# bmscableL431.net
KiCad netlist of a schematic drawn in EAGLE
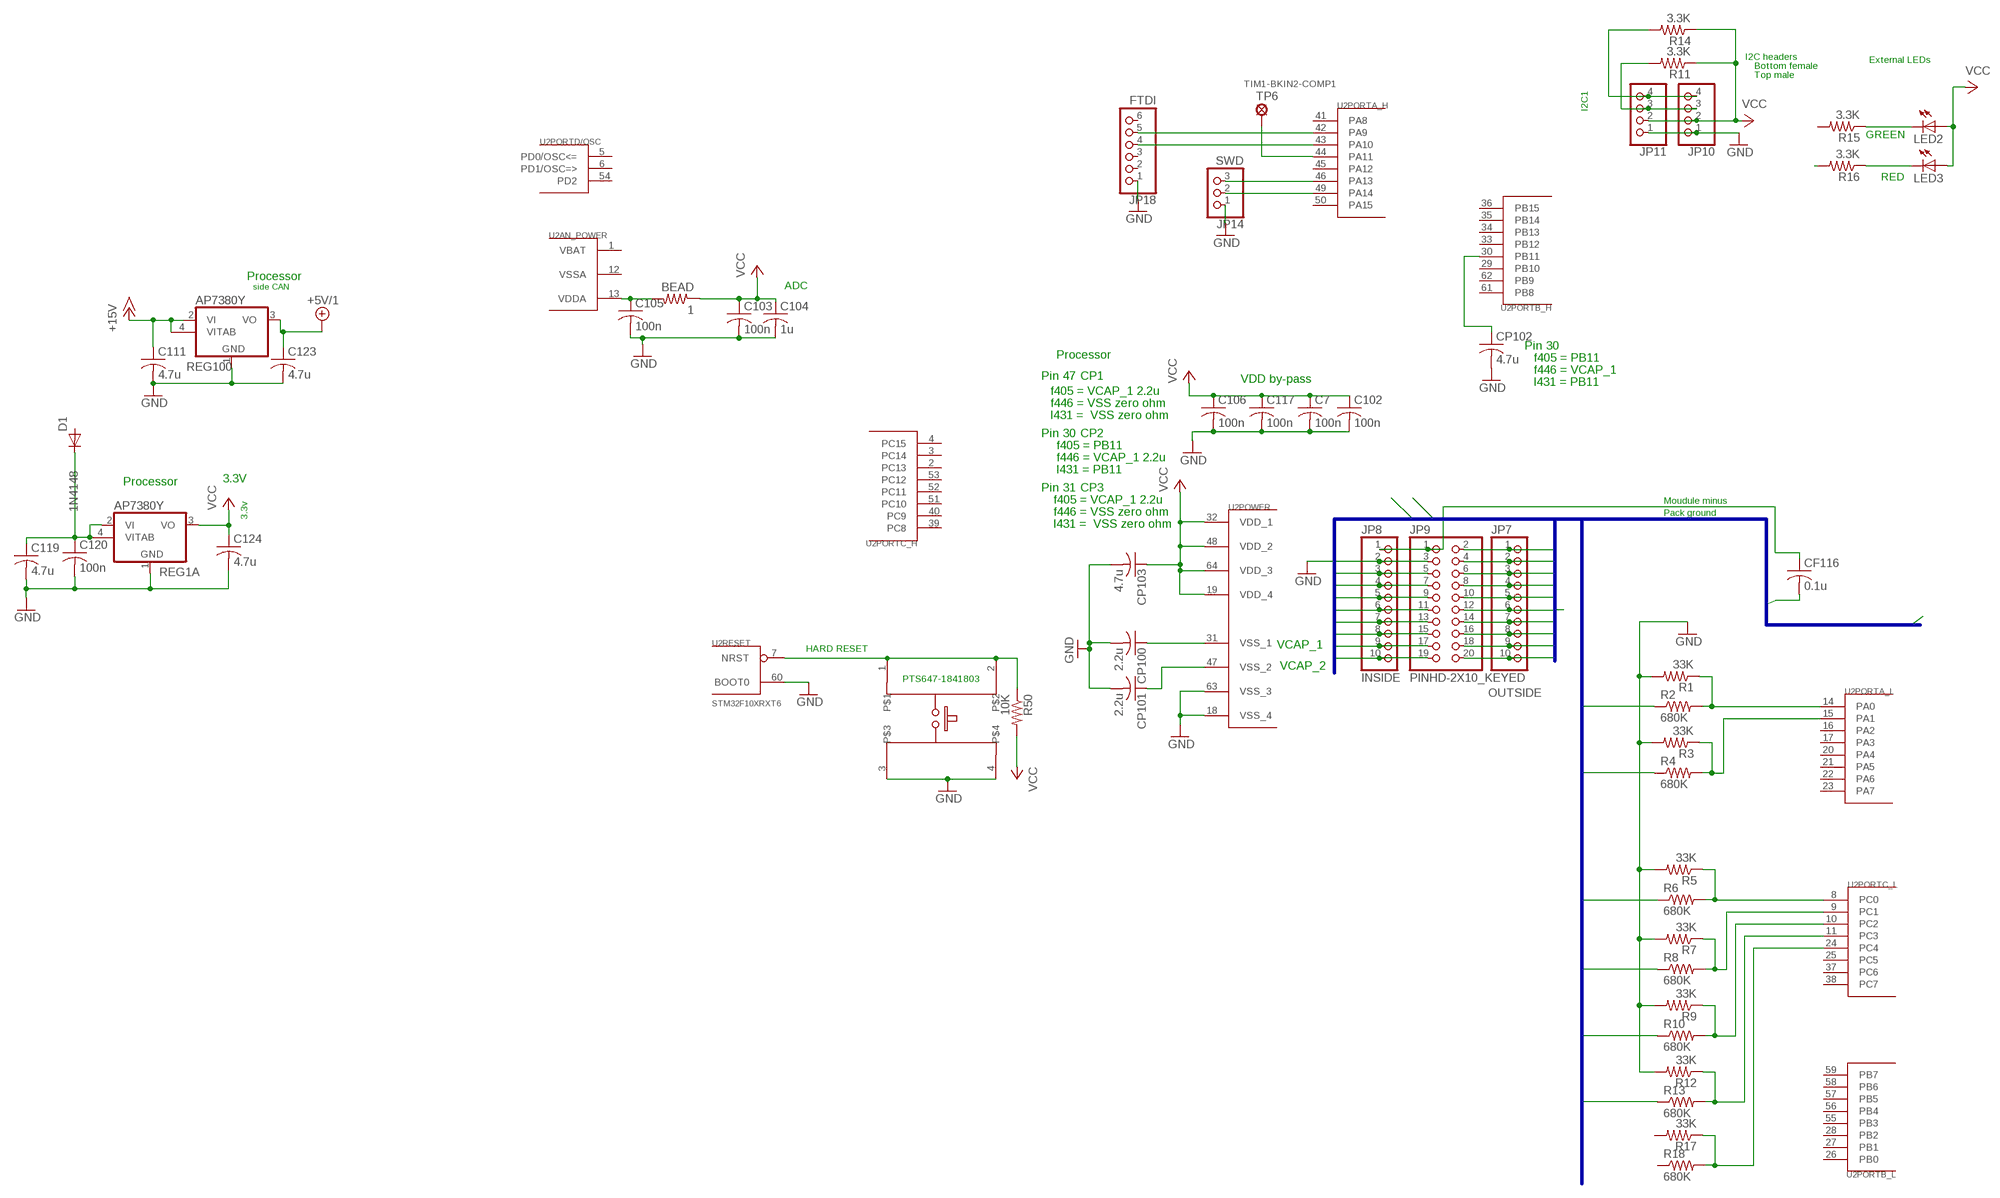
[diagram p0: schematic, sheet 1]

(export (version "E")
  (design (tool "Eeschema 10.0.6"))
  (components
    (comp (ref "BEAD")
      (value "1")
      (footprint "eagle-import:R0603")
      (libsource (lib "eagle-import") (part "R-US_R0603"))
    )
    (comp (ref "C7")
      (value "100n")
      (footprint "eagle-import:C0603")
      (libsource (lib "eagle-import") (part "C-USC0603"))
    )
    (comp (ref "C102")
      (value "100n")
      (footprint "eagle-import:C0603")
      (libsource (lib "eagle-import") (part "C-USC0603"))
    )
    (comp (ref "C103")
      (value "100n")
      (footprint "eagle-import:C0603")
      (libsource (lib "eagle-import") (part "C-USC0603"))
    )
    (comp (ref "C104")
      (value "1u")
      (footprint "eagle-import:C0603")
      (libsource (lib "eagle-import") (part "C-USC0603"))
    )
    (comp (ref "C105")
      (value "100n")
      (footprint "eagle-import:C0603")
      (libsource (lib "eagle-import") (part "C-USC0603"))
    )
    (comp (ref "C106")
      (value "100n")
      (footprint "eagle-import:C0603")
      (libsource (lib "eagle-import") (part "C-USC0603"))
    )
    (comp (ref "C111")
      (value "4.7u")
      (footprint "eagle-import:C0603")
      (libsource (lib "eagle-import") (part "C-USC0603"))
    )
    (comp (ref "C117")
      (value "100n")
      (footprint "eagle-import:C0603")
      (libsource (lib "eagle-import") (part "C-USC0603"))
    )
    (comp (ref "C119")
      (value "4.7u")
      (footprint "eagle-import:C0603")
      (libsource (lib "eagle-import") (part "C-USC0603"))
    )
    (comp (ref "C120")
      (value "100n")
      (footprint "eagle-import:C0603")
      (libsource (lib "eagle-import") (part "C-USC0603"))
    )
    (comp (ref "C123")
      (value "4.7u")
      (footprint "eagle-import:C0603")
      (libsource (lib "eagle-import") (part "C-USC0603"))
    )
    (comp (ref "C124")
      (value "4.7u")
      (footprint "eagle-import:C0805")
      (libsource (lib "eagle-import") (part "C-USC0805"))
    )
    (comp (ref "CF116")
      (value "0.1u")
      (footprint "eagle-import:C0603")
      (libsource (lib "eagle-import") (part "C-USC0603"))
    )
    (comp (ref "CP100")
      (value "2.2u")
      (footprint "eagle-import:C0603")
      (libsource (lib "eagle-import") (part "C-USC0603"))
    )
    (comp (ref "CP101")
      (value "2.2u")
      (footprint "eagle-import:C0603")
      (libsource (lib "eagle-import") (part "C-USC0603"))
    )
    (comp (ref "CP102")
      (value "4.7u")
      (footprint "eagle-import:C0603")
      (libsource (lib "eagle-import") (part "C-USC0603"))
    )
    (comp (ref "CP103")
      (value "4.7u")
      (footprint "eagle-import:C0603")
      (libsource (lib "eagle-import") (part "C-USC0603"))
    )
    (comp (ref "D1")
      (value "1N4148")
      (footprint "eagle-import:DO41-10_VERT")
      (libsource (lib "eagle-import") (part "1N4004_VERT"))
    )
    (comp (ref "JP7")
      (value "OUTSIDE")
      (footprint "eagle-import:1X10")
      (libsource (lib "eagle-import") (part "PINHD-1X10"))
    )
    (comp (ref "JP8")
      (value "INSIDE")
      (footprint "eagle-import:1X10")
      (libsource (lib "eagle-import") (part "PINHD-1X10"))
    )
    (comp (ref "JP9")
      (value "PINHD-2X10_KEYED")
      (footprint "eagle-import:2X10_KEYED")
      (libsource (lib "eagle-import") (part "PINHD-2X10_KEYED"))
    )
    (comp (ref "JP10")
      (value "PINHD-1X4")
      (footprint "eagle-import:1X04")
      (libsource (lib "eagle-import") (part "PINHD-1X4"))
    )
    (comp (ref "JP11")
      (value "PINHD-1X4")
      (footprint "eagle-import:1X04")
      (libsource (lib "eagle-import") (part "PINHD-1X4"))
    )
    (comp (ref "JP14")
      (value "SWD")
      (footprint "eagle-import:1X03")
      (libsource (lib "eagle-import") (part "PINHD-1X3"))
    )
    (comp (ref "JP18")
      (value "FTDI")
      (footprint "eagle-import:1X06")
      (libsource (lib "eagle-import") (part "PINHD-1X6"))
    )
    (comp (ref "LED2")
      (value "LEDCHIP-LED0603")
      (footprint "eagle-import:CHIP-LED0603")
      (libsource (lib "eagle-import") (part "LEDCHIP-LED0603"))
    )
    (comp (ref "LED3")
      (value "LEDCHIP-LED0603")
      (footprint "eagle-import:CHIP-LED0603")
      (libsource (lib "eagle-import") (part "LEDCHIP-LED0603"))
    )
    (comp (ref "R1")
      (value "33K")
      (footprint "eagle-import:R0603")
      (libsource (lib "eagle-import") (part "R-US_R0603"))
    )
    (comp (ref "R2")
      (value "680K")
      (footprint "eagle-import:R0603")
      (libsource (lib "eagle-import") (part "R-US_R0603"))
    )
    (comp (ref "R3")
      (value "33K")
      (footprint "eagle-import:R0603")
      (libsource (lib "eagle-import") (part "R-US_R0603"))
    )
    (comp (ref "R4")
      (value "680K")
      (footprint "eagle-import:R0603")
      (libsource (lib "eagle-import") (part "R-US_R0603"))
    )
    (comp (ref "R5")
      (value "33K")
      (footprint "eagle-import:R0603")
      (libsource (lib "eagle-import") (part "R-US_R0603"))
    )
    (comp (ref "R6")
      (value "680K")
      (footprint "eagle-import:R0603")
      (libsource (lib "eagle-import") (part "R-US_R0603"))
    )
    (comp (ref "R7")
      (value "33K")
      (footprint "eagle-import:R0603")
      (libsource (lib "eagle-import") (part "R-US_R0603"))
    )
    (comp (ref "R8")
      (value "680K")
      (footprint "eagle-import:R0603")
      (libsource (lib "eagle-import") (part "R-US_R0603"))
    )
    (comp (ref "R9")
      (value "33K")
      (footprint "eagle-import:R0603")
      (libsource (lib "eagle-import") (part "R-US_R0603"))
    )
    (comp (ref "R10")
      (value "680K")
      (footprint "eagle-import:R0603")
      (libsource (lib "eagle-import") (part "R-US_R0603"))
    )
    (comp (ref "R11")
      (value "3.3K")
      (footprint "eagle-import:R0603")
      (libsource (lib "eagle-import") (part "R-US_R0603"))
    )
    (comp (ref "R12")
      (value "33K")
      (footprint "eagle-import:R0603")
      (libsource (lib "eagle-import") (part "R-US_R0603"))
    )
    (comp (ref "R13")
      (value "680K")
      (footprint "eagle-import:R0603")
      (libsource (lib "eagle-import") (part "R-US_R0603"))
    )
    (comp (ref "R14")
      (value "3.3K")
      (footprint "eagle-import:R0603")
      (libsource (lib "eagle-import") (part "R-US_R0603"))
    )
    (comp (ref "R15")
      (value "3.3K")
      (footprint "eagle-import:R0603")
      (libsource (lib "eagle-import") (part "R-US_R0603"))
    )
    (comp (ref "R16")
      (value "3.3K")
      (footprint "eagle-import:R0603")
      (libsource (lib "eagle-import") (part "R-US_R0603"))
    )
    (comp (ref "R17")
      (value "33K")
      (footprint "eagle-import:R0603")
      (libsource (lib "eagle-import") (part "R-US_R0603"))
    )
    (comp (ref "R18")
      (value "680K")
      (footprint "eagle-import:R0603")
      (libsource (lib "eagle-import") (part "R-US_R0603"))
    )
    (comp (ref "R50")
      (value "10K")
      (footprint "eagle-import:R0603")
      (libsource (lib "eagle-import") (part "R-US_R0603"))
    )
    (comp (ref "REG1A")
      (value "AP7380Y")
      (footprint "eagle-import:SOT89")
      (libsource (lib "eagle-import") (part "AP7380Y"))
    )
    (comp (ref "REG100")
      (value "AP7380Y")
      (footprint "eagle-import:SOT89")
      (libsource (lib "eagle-import") (part "AP7380Y"))
    )
    (comp (ref "TP6")
      (value "SOLDPAD0.6MM")
      (footprint "eagle-import:SOLPAD.6MM")
      (libsource (lib "eagle-import") (part "SOLDPAD0.6MM"))
    )
    (comp (ref "U$1")
      (value "E-SWITCH2")
      (footprint "eagle-import:E-SWITCH2")
      (libsource (lib "eagle-import") (part "E-SWITCH2"))
    )
    (comp (ref "U2")
      (value "STM32F10XRXT6")
      (footprint "eagle-import:TQFP64")
      (libsource (lib "eagle-import") (part "STM32F10XRXT6"))
    )
  )
  (nets
    (net (code "1") (name "+5V{slash}1") (class "Default")
      (node (ref "C123") (pin "1") (pinfunction "1_1") (pintype "passive"))
      (node (ref "REG100") (pin "3") (pinfunction "VO_3") (pintype "passive"))
    )
    (net (code "2") (name "+15V") (class "Default")
      (node (ref "C111") (pin "1") (pinfunction "1_1") (pintype "passive"))
      (node (ref "REG100") (pin "2") (pinfunction "VI_2") (pintype "input"))
      (node (ref "REG100") (pin "4") (pinfunction "VITAB_4") (pintype "bidirectional"))
    )
    (net (code "3") (name "/C1") (class "Default")
      (node (ref "JP8") (pin "7") (pinfunction "7_7") (pintype "passive"))
      (node (ref "JP9") (pin "13") (pinfunction "13_13") (pintype "passive"))
    )
    (net (code "4") (name "/C3") (class "Default")
      (node (ref "JP7") (pin "7") (pinfunction "7_7") (pintype "passive"))
      (node (ref "JP9") (pin "14") (pinfunction "14_14") (pintype "passive"))
      (node (ref "R4") (pin "1") (pinfunction "1_1") (pintype "passive"))
    )
    (net (code "5") (name "/C5") (class "Default")
      (node (ref "JP8") (pin "8") (pinfunction "8_8") (pintype "passive"))
      (node (ref "JP9") (pin "15") (pinfunction "15_15") (pintype "passive"))
      (node (ref "R2") (pin "1") (pinfunction "1_1") (pintype "passive"))
    )
    (net (code "6") (name "/C7") (class "Default")
      (node (ref "JP7") (pin "8") (pinfunction "8_8") (pintype "passive"))
      (node (ref "JP9") (pin "16") (pinfunction "16_16") (pintype "passive"))
      (node (ref "R13") (pin "1") (pinfunction "1_1") (pintype "passive"))
    )
    (net (code "7") (name "/C9") (class "Default")
      (node (ref "JP8") (pin "9") (pinfunction "9_9") (pintype "passive"))
      (node (ref "JP9") (pin "17") (pinfunction "17_17") (pintype "passive"))
      (node (ref "R10") (pin "1") (pinfunction "1_1") (pintype "passive"))
    )
    (net (code "8") (name "/C11") (class "Default")
      (node (ref "JP7") (pin "9") (pinfunction "9_9") (pintype "passive"))
      (node (ref "JP9") (pin "18") (pinfunction "18_18") (pintype "passive"))
      (node (ref "R8") (pin "1") (pinfunction "1_1") (pintype "passive"))
    )
    (net (code "9") (name "/C13") (class "Default")
      (node (ref "JP8") (pin "10") (pinfunction "10_10") (pintype "passive"))
      (node (ref "JP9") (pin "19") (pinfunction "19_19") (pintype "passive"))
      (node (ref "R6") (pin "1") (pinfunction "1_1") (pintype "passive"))
    )
    (net (code "10") (name "/C16") (class "Default")
      (node (ref "JP7") (pin "6") (pinfunction "6_6") (pintype "passive"))
      (node (ref "JP9") (pin "12") (pinfunction "12_12") (pintype "passive"))
    )
    (net (code "11") (name "/SRP") (class "Default")
      (node (ref "CF116") (pin "2") (pinfunction "2_2") (pintype "passive"))
      (node (ref "JP7") (pin "1") (pinfunction "1_1") (pintype "passive"))
      (node (ref "JP9") (pin "2") (pinfunction "2_2") (pintype "passive"))
    )
    (net (code "12") (name "/VBAT") (class "Default")
      (node (ref "U2") (pin "1") (pinfunction "VBAT_1") (pintype "power_in"))
    )
    (net (code "13") (name "/VSSA") (class "Default")
      (node (ref "U2") (pin "12") (pinfunction "VSSA_12") (pintype "power_in"))
    )
    (net (code "14") (name "GND") (class "Default")
      (node (ref "C102") (pin "2") (pinfunction "2_2") (pintype "passive"))
      (node (ref "C103") (pin "2") (pinfunction "2_2") (pintype "passive"))
      (node (ref "C104") (pin "2") (pinfunction "2_2") (pintype "passive"))
      (node (ref "C105") (pin "2") (pinfunction "2_2") (pintype "passive"))
      (node (ref "C106") (pin "2") (pinfunction "2_2") (pintype "passive"))
      (node (ref "C111") (pin "2") (pinfunction "2_2") (pintype "passive"))
      (node (ref "C117") (pin "2") (pinfunction "2_2") (pintype "passive"))
      (node (ref "C119") (pin "2") (pinfunction "2_2") (pintype "passive"))
      (node (ref "C120") (pin "2") (pinfunction "2_2") (pintype "passive"))
      (node (ref "C123") (pin "2") (pinfunction "2_2") (pintype "passive"))
      (node (ref "C124") (pin "2") (pinfunction "2_2") (pintype "passive"))
      (node (ref "C7") (pin "2") (pinfunction "2_2") (pintype "passive"))
      (node (ref "CP100") (pin "2") (pinfunction "2_2") (pintype "passive"))
      (node (ref "CP101") (pin "2") (pinfunction "2_2") (pintype "passive"))
      (node (ref "CP102") (pin "2") (pinfunction "2_2") (pintype "passive"))
      (node (ref "CP103") (pin "2") (pinfunction "2_2") (pintype "passive"))
      (node (ref "JP10") (pin "1") (pinfunction "1_1") (pintype "passive"))
      (node (ref "JP11") (pin "1") (pinfunction "1_1") (pintype "passive"))
      (node (ref "JP14") (pin "1") (pinfunction "1_1") (pintype "passive"))
      (node (ref "JP18") (pin "1") (pinfunction "1_1") (pintype "passive"))
      (node (ref "JP8") (pin "2") (pinfunction "2_2") (pintype "passive"))
      (node (ref "JP9") (pin "3") (pinfunction "3_3") (pintype "passive"))
      (node (ref "R1") (pin "2") (pinfunction "2_2") (pintype "passive"))
      (node (ref "R12") (pin "2") (pinfunction "2_2") (pintype "passive"))
      (node (ref "R3") (pin "2") (pinfunction "2_2") (pintype "passive"))
      (node (ref "R5") (pin "2") (pinfunction "2_2") (pintype "passive"))
      (node (ref "R7") (pin "2") (pinfunction "2_2") (pintype "passive"))
      (node (ref "R9") (pin "2") (pinfunction "2_2") (pintype "passive"))
      (node (ref "REG100") (pin "1") (pinfunction "GND_1") (pintype "passive"))
      (node (ref "REG1A") (pin "1") (pinfunction "GND_1") (pintype "passive"))
      (node (ref "U$1") (pin "3") (pinfunction "P$3_3") (pintype "bidirectional"))
      (node (ref "U$1") (pin "4") (pinfunction "P$4_4") (pintype "bidirectional"))
      (node (ref "U2") (pin "18") (pinfunction "VSS_4_18") (pintype "power_in"))
      (node (ref "U2") (pin "60") (pinfunction "BOOT0_60") (pintype "input"))
      (node (ref "U2") (pin "63") (pinfunction "VSS_3_63") (pintype "power_in"))
    )
    (net (code "15") (name "Net-(CF116-Pad1)") (class "Default")
      (node (ref "CF116") (pin "1") (pinfunction "1_1") (pintype "passive"))
      (node (ref "JP8") (pin "1") (pinfunction "1_1") (pintype "passive"))
      (node (ref "JP9") (pin "1") (pinfunction "1_1") (pintype "passive"))
    )
    (net (code "16") (name "Net-(JP7-Pad2)") (class "Default")
      (node (ref "JP7") (pin "2") (pinfunction "2_2") (pintype "passive"))
      (node (ref "JP9") (pin "4") (pinfunction "4_4") (pintype "passive"))
    )
    (net (code "17") (name "Net-(JP7-Pad3)") (class "Default")
      (node (ref "JP7") (pin "3") (pinfunction "3_3") (pintype "passive"))
      (node (ref "JP9") (pin "6") (pinfunction "6_6") (pintype "passive"))
    )
    (net (code "18") (name "Net-(JP7-Pad4)") (class "Default")
      (node (ref "JP7") (pin "4") (pinfunction "4_4") (pintype "passive"))
      (node (ref "JP9") (pin "8") (pinfunction "8_8") (pintype "passive"))
    )
    (net (code "19") (name "Net-(JP7-Pad5)") (class "Default")
      (node (ref "JP7") (pin "5") (pinfunction "5_5") (pintype "passive"))
      (node (ref "JP9") (pin "10") (pinfunction "10_10") (pintype "passive"))
    )
    (net (code "20") (name "Net-(JP7-Pad10)") (class "Default")
      (node (ref "JP7") (pin "10") (pinfunction "10_10") (pintype "passive"))
      (node (ref "JP9") (pin "20") (pinfunction "20_20") (pintype "passive"))
    )
    (net (code "21") (name "Net-(JP8-Pad3)") (class "Default")
      (node (ref "JP8") (pin "3") (pinfunction "3_3") (pintype "passive"))
      (node (ref "JP9") (pin "5") (pinfunction "5_5") (pintype "passive"))
    )
    (net (code "22") (name "Net-(JP8-Pad4)") (class "Default")
      (node (ref "JP8") (pin "4") (pinfunction "4_4") (pintype "passive"))
      (node (ref "JP9") (pin "7") (pinfunction "7_7") (pintype "passive"))
    )
    (net (code "23") (name "Net-(JP8-Pad5)") (class "Default")
      (node (ref "JP8") (pin "5") (pinfunction "5_5") (pintype "passive"))
      (node (ref "JP9") (pin "9") (pinfunction "9_9") (pintype "passive"))
    )
    (net (code "24") (name "Net-(JP8-Pad6)") (class "Default")
      (node (ref "JP8") (pin "6") (pinfunction "6_6") (pintype "passive"))
      (node (ref "JP9") (pin "11") (pinfunction "11_11") (pintype "passive"))
    )
    (net (code "25") (name "Net-(JP10-Pad3)") (class "Default")
      (node (ref "JP10") (pin "3") (pinfunction "3_3") (pintype "passive"))
      (node (ref "JP11") (pin "3") (pinfunction "3_3") (pintype "passive"))
      (node (ref "R11") (pin "2") (pinfunction "2_2") (pintype "passive"))
    )
    (net (code "26") (name "Net-(JP10-Pad4)") (class "Default")
      (node (ref "JP10") (pin "4") (pinfunction "4_4") (pintype "passive"))
      (node (ref "JP11") (pin "4") (pinfunction "4_4") (pintype "passive"))
      (node (ref "R14") (pin "2") (pinfunction "2_2") (pintype "passive"))
    )
    (net (code "27") (name "Net-(LED2-PadC)") (class "Default")
      (node (ref "LED2") (pin "C") (pinfunction "C_C") (pintype "passive"))
      (node (ref "R15") (pin "1") (pinfunction "1_1") (pintype "passive"))
    )
    (net (code "28") (name "Net-(LED3-PadC)") (class "Default")
      (node (ref "LED3") (pin "C") (pinfunction "C_C") (pintype "passive"))
      (node (ref "R16") (pin "1") (pinfunction "1_1") (pintype "passive"))
    )
    (net (code "29") (name "Net-(REG1A-VI)") (class "Default")
      (node (ref "C119") (pin "1") (pinfunction "1_1") (pintype "passive"))
      (node (ref "C120") (pin "1") (pinfunction "1_1") (pintype "passive"))
      (node (ref "D1") (pin "C") (pinfunction "C_C") (pintype "passive"))
      (node (ref "REG1A") (pin "2") (pinfunction "VI_2") (pintype "input"))
      (node (ref "REG1A") (pin "4") (pinfunction "VITAB_4") (pintype "bidirectional"))
    )
    (net (code "30") (name "Net-(U$1-P$1)") (class "Default")
      (node (ref "R50") (pin "1") (pinfunction "1_1") (pintype "passive"))
      (node (ref "U$1") (pin "1") (pinfunction "P$1_1") (pintype "bidirectional"))
      (node (ref "U$1") (pin "2") (pinfunction "P$2_2") (pintype "bidirectional"))
      (node (ref "U2") (pin "7") (pinfunction "NRST_7") (pintype "input"))
    )
    (net (code "31") (name "Net-(U2A-VDDA)") (class "Default")
      (node (ref "BEAD") (pin "2") (pinfunction "2_2") (pintype "passive"))
      (node (ref "C105") (pin "1") (pinfunction "1_1") (pintype "passive"))
      (node (ref "U2") (pin "13") (pinfunction "VDDA_13") (pintype "power_in"))
    )
    (net (code "32") (name "Net-(U2B-PA9)") (class "Default")
      (node (ref "JP18") (pin "5") (pinfunction "5_5") (pintype "passive"))
      (node (ref "U2") (pin "42") (pinfunction "PA9_42") (pintype "bidirectional"))
    )
    (net (code "33") (name "Net-(U2B-PA10)") (class "Default")
      (node (ref "JP18") (pin "4") (pinfunction "4_4") (pintype "passive"))
      (node (ref "U2") (pin "43") (pinfunction "PA10_43") (pintype "bidirectional"))
    )
    (net (code "34") (name "Net-(U2B-PA11)") (class "Default")
      (node (ref "TP6") (pin "MP") (pinfunction "MP_MP") (pintype "passive"))
      (node (ref "U2") (pin "44") (pinfunction "PA11_44") (pintype "bidirectional"))
    )
    (net (code "35") (name "Net-(U2B-PA13)") (class "Default")
      (node (ref "JP14") (pin "3") (pinfunction "3_3") (pintype "passive"))
      (node (ref "U2") (pin "46") (pinfunction "PA13_46") (pintype "bidirectional"))
    )
    (net (code "36") (name "Net-(U2B-PA14)") (class "Default")
      (node (ref "JP14") (pin "2") (pinfunction "2_2") (pintype "passive"))
      (node (ref "U2") (pin "49") (pinfunction "PA14_49") (pintype "bidirectional"))
    )
    (net (code "37") (name "Net-(U2C-PA0)") (class "Default")
      (node (ref "R1") (pin "1") (pinfunction "1_1") (pintype "passive"))
      (node (ref "R2") (pin "2") (pinfunction "2_2") (pintype "passive"))
      (node (ref "U2") (pin "14") (pinfunction "PA0_14") (pintype "bidirectional"))
    )
    (net (code "38") (name "Net-(U2C-PA1)") (class "Default")
      (node (ref "R3") (pin "1") (pinfunction "1_1") (pintype "passive"))
      (node (ref "R4") (pin "2") (pinfunction "2_2") (pintype "passive"))
      (node (ref "U2") (pin "15") (pinfunction "PA1_15") (pintype "bidirectional"))
    )
    (net (code "39") (name "Net-(U2D-PB11)") (class "Default")
      (node (ref "CP102") (pin "1") (pinfunction "1_1") (pintype "passive"))
      (node (ref "U2") (pin "30") (pinfunction "PB11_30") (pintype "bidirectional"))
    )
    (net (code "40") (name "Net-(U2G-PC0)") (class "Default")
      (node (ref "R5") (pin "1") (pinfunction "1_1") (pintype "passive"))
      (node (ref "R6") (pin "2") (pinfunction "2_2") (pintype "passive"))
      (node (ref "U2") (pin "8") (pinfunction "PC0_8") (pintype "bidirectional"))
    )
    (net (code "41") (name "Net-(U2G-PC1)") (class "Default")
      (node (ref "R7") (pin "1") (pinfunction "1_1") (pintype "passive"))
      (node (ref "R8") (pin "2") (pinfunction "2_2") (pintype "passive"))
      (node (ref "U2") (pin "9") (pinfunction "PC1_9") (pintype "bidirectional"))
    )
    (net (code "42") (name "Net-(U2G-PC2)") (class "Default")
      (node (ref "R10") (pin "2") (pinfunction "2_2") (pintype "passive"))
      (node (ref "R9") (pin "1") (pinfunction "1_1") (pintype "passive"))
      (node (ref "U2") (pin "10") (pinfunction "PC2_10") (pintype "bidirectional"))
    )
    (net (code "43") (name "Net-(U2G-PC3)") (class "Default")
      (node (ref "R12") (pin "1") (pinfunction "1_1") (pintype "passive"))
      (node (ref "R13") (pin "2") (pinfunction "2_2") (pintype "passive"))
      (node (ref "U2") (pin "11") (pinfunction "PC3_11") (pintype "bidirectional"))
    )
    (net (code "44") (name "Net-(U2G-PC4)") (class "Default")
      (node (ref "R17") (pin "1") (pinfunction "1_1") (pintype "passive"))
      (node (ref "R18") (pin "2") (pinfunction "2_2") (pintype "passive"))
      (node (ref "U2") (pin "24") (pinfunction "PC4_24") (pintype "bidirectional"))
    )
    (net (code "45") (name "Net-(U2I-VSS_1)") (class "Default")
      (node (ref "CP100") (pin "1") (pinfunction "1_1") (pintype "passive"))
      (node (ref "U2") (pin "31") (pinfunction "VSS_1_31") (pintype "power_in"))
    )
    (net (code "46") (name "Net-(U2I-VSS_2)") (class "Default")
      (node (ref "CP101") (pin "1") (pinfunction "1_1") (pintype "passive"))
      (node (ref "U2") (pin "47") (pinfunction "VSS_2_47") (pintype "power_in"))
    )
    (net (code "47") (name "VCC") (class "Default")
      (node (ref "BEAD") (pin "1") (pinfunction "1_1") (pintype "passive"))
      (node (ref "C102") (pin "1") (pinfunction "1_1") (pintype "passive"))
      (node (ref "C103") (pin "1") (pinfunction "1_1") (pintype "passive"))
      (node (ref "C104") (pin "1") (pinfunction "1_1") (pintype "passive"))
      (node (ref "C106") (pin "1") (pinfunction "1_1") (pintype "passive"))
      (node (ref "C117") (pin "1") (pinfunction "1_1") (pintype "passive"))
      (node (ref "C124") (pin "1") (pinfunction "1_1") (pintype "passive"))
      (node (ref "C7") (pin "1") (pinfunction "1_1") (pintype "passive"))
      (node (ref "CP103") (pin "1") (pinfunction "1_1") (pintype "passive"))
      (node (ref "JP10") (pin "2") (pinfunction "2_2") (pintype "passive"))
      (node (ref "JP11") (pin "2") (pinfunction "2_2") (pintype "passive"))
      (node (ref "LED2") (pin "A") (pinfunction "A_A") (pintype "passive"))
      (node (ref "LED3") (pin "A") (pinfunction "A_A") (pintype "passive"))
      (node (ref "R11") (pin "1") (pinfunction "1_1") (pintype "passive"))
      (node (ref "R14") (pin "1") (pinfunction "1_1") (pintype "passive"))
      (node (ref "R50") (pin "2") (pinfunction "2_2") (pintype "passive"))
      (node (ref "REG1A") (pin "3") (pinfunction "VO_3") (pintype "passive"))
      (node (ref "U2") (pin "19") (pinfunction "VDD_4_19") (pintype "power_in"))
      (node (ref "U2") (pin "32") (pinfunction "VDD_1_32") (pintype "power_in"))
      (node (ref "U2") (pin "48") (pinfunction "VDD_2_48") (pintype "power_in"))
      (node (ref "U2") (pin "64") (pinfunction "VDD_3_64") (pintype "power_in"))
    )
    (net (code "48") (name "unconnected-(D1-PadA)") (class "Default")
      (node (ref "D1") (pin "A") (pinfunction "A_A") (pintype "passive"))
    )
    (net (code "49") (name "unconnected-(JP18-Pad2)") (class "Default")
      (node (ref "JP18") (pin "2") (pinfunction "2_2") (pintype "passive"))
    )
    (net (code "50") (name "unconnected-(JP18-Pad3)") (class "Default")
      (node (ref "JP18") (pin "3") (pinfunction "3_3") (pintype "passive"))
    )
    (net (code "51") (name "unconnected-(JP18-Pad6)") (class "Default")
      (node (ref "JP18") (pin "6") (pinfunction "6_6") (pintype "passive"))
    )
    (net (code "52") (name "unconnected-(R15-Pad2)") (class "Default")
      (node (ref "R15") (pin "2") (pinfunction "2_2") (pintype "passive"))
    )
    (net (code "53") (name "unconnected-(R16-Pad2)") (class "Default")
      (node (ref "R16") (pin "2") (pinfunction "2_2") (pintype "passive"))
    )
    (net (code "54") (name "unconnected-(R17-Pad2)") (class "Default")
      (node (ref "R17") (pin "2") (pinfunction "2_2") (pintype "passive"))
    )
    (net (code "55") (name "unconnected-(R18-Pad1)") (class "Default")
      (node (ref "R18") (pin "1") (pinfunction "1_1") (pintype "passive"))
    )
    (net (code "56") (name "unconnected-(U2B-PA8-Pad41)") (class "Default")
      (node (ref "U2") (pin "41") (pinfunction "PA8_41") (pintype "bidirectional"))
    )
    (net (code "57") (name "unconnected-(U2B-PA12-Pad45)") (class "Default")
      (node (ref "U2") (pin "45") (pinfunction "PA12_45") (pintype "bidirectional"))
    )
    (net (code "58") (name "unconnected-(U2B-PA15-Pad50)") (class "Default")
      (node (ref "U2") (pin "50") (pinfunction "PA15_50") (pintype "bidirectional"))
    )
    (net (code "59") (name "unconnected-(U2C-PA2-Pad16)") (class "Default")
      (node (ref "U2") (pin "16") (pinfunction "PA2_16") (pintype "bidirectional"))
    )
    (net (code "60") (name "unconnected-(U2C-PA3-Pad17)") (class "Default")
      (node (ref "U2") (pin "17") (pinfunction "PA3_17") (pintype "bidirectional"))
    )
    (net (code "61") (name "unconnected-(U2C-PA4-Pad20)") (class "Default")
      (node (ref "U2") (pin "20") (pinfunction "PA4_20") (pintype "bidirectional"))
    )
    (net (code "62") (name "unconnected-(U2C-PA5-Pad21)") (class "Default")
      (node (ref "U2") (pin "21") (pinfunction "PA5_21") (pintype "bidirectional"))
    )
    (net (code "63") (name "unconnected-(U2C-PA6-Pad22)") (class "Default")
      (node (ref "U2") (pin "22") (pinfunction "PA6_22") (pintype "bidirectional"))
    )
    (net (code "64") (name "unconnected-(U2C-PA7-Pad23)") (class "Default")
      (node (ref "U2") (pin "23") (pinfunction "PA7_23") (pintype "bidirectional"))
    )
    (net (code "65") (name "unconnected-(U2D-PB8-Pad61)") (class "Default")
      (node (ref "U2") (pin "61") (pinfunction "PB8_61") (pintype "bidirectional"))
    )
    (net (code "66") (name "unconnected-(U2D-PB9-Pad62)") (class "Default")
      (node (ref "U2") (pin "62") (pinfunction "PB9_62") (pintype "bidirectional"))
    )
    (net (code "67") (name "unconnected-(U2D-PB10-Pad29)") (class "Default")
      (node (ref "U2") (pin "29") (pinfunction "PB10_29") (pintype "bidirectional"))
    )
    (net (code "68") (name "unconnected-(U2D-PB12-Pad33)") (class "Default")
      (node (ref "U2") (pin "33") (pinfunction "PB12_33") (pintype "bidirectional"))
    )
    (net (code "69") (name "unconnected-(U2D-PB13-Pad34)") (class "Default")
      (node (ref "U2") (pin "34") (pinfunction "PB13_34") (pintype "bidirectional"))
    )
    (net (code "70") (name "unconnected-(U2D-PB14-Pad35)") (class "Default")
      (node (ref "U2") (pin "35") (pinfunction "PB14_35") (pintype "bidirectional"))
    )
    (net (code "71") (name "unconnected-(U2D-PB15-Pad36)") (class "Default")
      (node (ref "U2") (pin "36") (pinfunction "PB15_36") (pintype "bidirectional"))
    )
    (net (code "72") (name "unconnected-(U2E-PB0-Pad26)") (class "Default")
      (node (ref "U2") (pin "26") (pinfunction "PB0_26") (pintype "bidirectional"))
    )
    (net (code "73") (name "unconnected-(U2E-PB1-Pad27)") (class "Default")
      (node (ref "U2") (pin "27") (pinfunction "PB1_27") (pintype "bidirectional"))
    )
    (net (code "74") (name "unconnected-(U2E-PB2-Pad28)") (class "Default")
      (node (ref "U2") (pin "28") (pinfunction "PB2_28") (pintype "bidirectional"))
    )
    (net (code "75") (name "unconnected-(U2E-PB3-Pad55)") (class "Default")
      (node (ref "U2") (pin "55") (pinfunction "PB3_55") (pintype "bidirectional"))
    )
    (net (code "76") (name "unconnected-(U2E-PB4-Pad56)") (class "Default")
      (node (ref "U2") (pin "56") (pinfunction "PB4_56") (pintype "bidirectional"))
    )
    (net (code "77") (name "unconnected-(U2E-PB5-Pad57)") (class "Default")
      (node (ref "U2") (pin "57") (pinfunction "PB5_57") (pintype "bidirectional"))
    )
    (net (code "78") (name "unconnected-(U2E-PB6-Pad58)") (class "Default")
      (node (ref "U2") (pin "58") (pinfunction "PB6_58") (pintype "bidirectional"))
    )
    (net (code "79") (name "unconnected-(U2E-PB7-Pad59)") (class "Default")
      (node (ref "U2") (pin "59") (pinfunction "PB7_59") (pintype "bidirectional"))
    )
    (net (code "80") (name "unconnected-(U2F-PC8-Pad39)") (class "Default")
      (node (ref "U2") (pin "39") (pinfunction "PC8_39") (pintype "bidirectional"))
    )
    (net (code "81") (name "unconnected-(U2F-PC9-Pad40)") (class "Default")
      (node (ref "U2") (pin "40") (pinfunction "PC9_40") (pintype "bidirectional"))
    )
    (net (code "82") (name "unconnected-(U2F-PC10-Pad51)") (class "Default")
      (node (ref "U2") (pin "51") (pinfunction "PC10_51") (pintype "bidirectional"))
    )
    (net (code "83") (name "unconnected-(U2F-PC11-Pad52)") (class "Default")
      (node (ref "U2") (pin "52") (pinfunction "PC11_52") (pintype "bidirectional"))
    )
    (net (code "84") (name "unconnected-(U2F-PC12-Pad53)") (class "Default")
      (node (ref "U2") (pin "53") (pinfunction "PC12_53") (pintype "bidirectional"))
    )
    (net (code "85") (name "unconnected-(U2F-PC13-Pad2)") (class "Default")
      (node (ref "U2") (pin "2") (pinfunction "PC13_2") (pintype "bidirectional"))
    )
    (net (code "86") (name "unconnected-(U2F-PC14-Pad3)") (class "Default")
      (node (ref "U2") (pin "3") (pinfunction "PC14_3") (pintype "bidirectional"))
    )
    (net (code "87") (name "unconnected-(U2F-PC15-Pad4)") (class "Default")
      (node (ref "U2") (pin "4") (pinfunction "PC15_4") (pintype "bidirectional"))
    )
    (net (code "88") (name "unconnected-(U2G-PC5-Pad25)") (class "Default")
      (node (ref "U2") (pin "25") (pinfunction "PC5_25") (pintype "bidirectional"))
    )
    (net (code "89") (name "unconnected-(U2G-PC6-Pad37)") (class "Default")
      (node (ref "U2") (pin "37") (pinfunction "PC6_37") (pintype "bidirectional"))
    )
    (net (code "90") (name "unconnected-(U2G-PC7-Pad38)") (class "Default")
      (node (ref "U2") (pin "38") (pinfunction "PC7_38") (pintype "bidirectional"))
    )
    (net (code "91") (name "unconnected-(U2H-PD0{slash}OSC<=-Pad5)") (class "Default")
      (node (ref "U2") (pin "5") (pinfunction "PD0/OSC<=_5") (pintype "bidirectional"))
    )
    (net (code "92") (name "unconnected-(U2H-PD1{slash}OSC=>-Pad6)") (class "Default")
      (node (ref "U2") (pin "6") (pinfunction "PD1/OSC=>_6") (pintype "bidirectional"))
    )
    (net (code "93") (name "unconnected-(U2H-PD2-Pad54)") (class "Default")
      (node (ref "U2") (pin "54") (pinfunction "PD2_54") (pintype "bidirectional"))
    )
  )
)
